# Kosmos-X3000-FM-Superregen.net
KiCad netlist of a schematic drawn in EAGLE
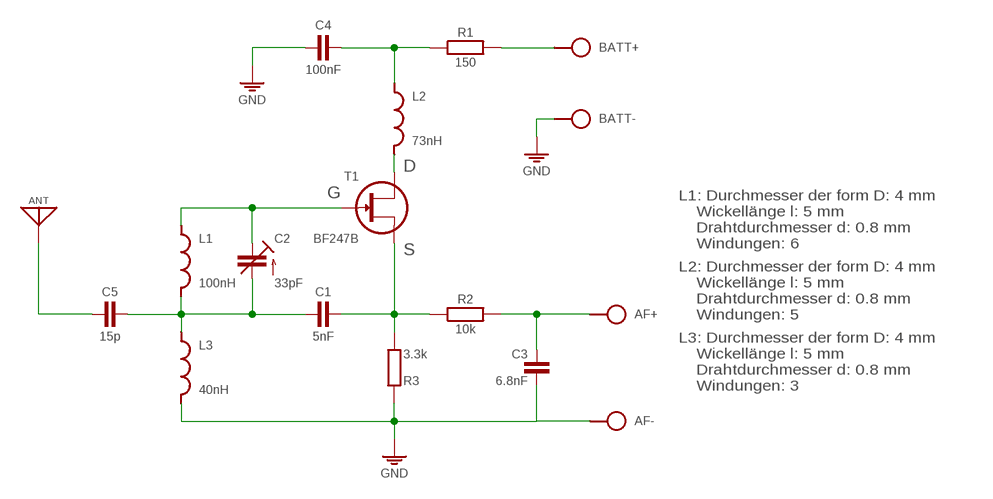
[diagram p0: schematic, sheet 1]

(export (version "E")
  (design (tool "Eeschema 10.0.6"))
  (components
    (comp (ref "AF")
      (value "SPAD+-+-")
      (footprint "eagle-import:SPAD+-")
      (libsource (lib "eagle-import") (part "SPAD+-+-"))
    )
    (comp (ref "ANT")
      (value "ANT")
      (footprint "eagle-import:SPAD")
      (libsource (lib "eagle-import") (part "ANT"))
    )
    (comp (ref "BATT")
      (value "SPAD+-+-")
      (footprint "eagle-import:SPAD+-")
      (libsource (lib "eagle-import") (part "SPAD+-+-"))
    )
    (comp (ref "C1")
      (value "5nF")
      (footprint "eagle-import:C050-020X044")
      (libsource (lib "eagle-import") (part "C050-020X044"))
    )
    (comp (ref "C2")
      (value "33pF")
      (footprint "eagle-import:TRIM-2222-808")
      (libsource (lib "eagle-import") (part "C-TR-PH201272222-808-2PIN"))
    )
    (comp (ref "C3")
      (value "6.8nF")
      (footprint "eagle-import:C050-020X044")
      (libsource (lib "eagle-import") (part "C050-020X044"))
    )
    (comp (ref "C4")
      (value "100nF")
      (footprint "eagle-import:C050-020X044")
      (libsource (lib "eagle-import") (part "C050-020X044"))
    )
    (comp (ref "C5")
      (value "15p")
      (footprint "eagle-import:C025-015X024")
      (libsource (lib "eagle-import") (part "C025-015X024"))
    )
    (comp (ref "L1")
      (value "100nH")
      (footprint "eagle-import:L-04-5_5V")
      (libsource (lib "eagle-import") (part "L-SHORT04-5/5V"))
    )
    (comp (ref "L2")
      (value "73nH")
      (footprint "eagle-import:L-04-5_5V")
      (libsource (lib "eagle-import") (part "L-SHORT04-5/5V"))
    )
    (comp (ref "L3")
      (value "40nH")
      (footprint "eagle-import:L-04-5_5V")
      (libsource (lib "eagle-import") (part "L-SHORT04-5/5V"))
    )
    (comp (ref "R1")
      (value "150")
      (footprint "eagle-import:0202_7-V")
      (libsource (lib "eagle-import") (part "R-H0202/7-V"))
    )
    (comp (ref "R2")
      (value "10k")
      (footprint "eagle-import:0202_7")
      (libsource (lib "eagle-import") (part "R-H0202/7"))
    )
    (comp (ref "R3")
      (value "3.3k")
      (footprint "eagle-import:0202_7")
      (libsource (lib "eagle-import") (part "R0202/7"))
    )
    (comp (ref "T1")
      (value "BF247B")
      (footprint "eagle-import:TO92")
      (libsource (lib "eagle-import") (part "BF247B"))
    )
  )
  (nets
    (net (code "1") (name "GND") (class "Default")
      (node (ref "AF") (pin "1") (pinfunction "P$1_1") (pintype "passive"))
      (node (ref "BATT") (pin "1") (pinfunction "P$1_1") (pintype "passive"))
      (node (ref "C3") (pin "2") (pinfunction "2_2") (pintype "passive"))
      (node (ref "C4") (pin "2") (pinfunction "2_2") (pintype "passive"))
      (node (ref "L3") (pin "1") (pinfunction "1_1") (pintype "passive"))
      (node (ref "R3") (pin "2") (pinfunction "1_2") (pintype "passive"))
    )
    (net (code "2") (name "Net-(AFA-P$1)") (class "Default")
      (node (ref "AF") (pin "2") (pinfunction "P$1_2") (pintype "passive"))
      (node (ref "C3") (pin "1") (pinfunction "1_1") (pintype "passive"))
      (node (ref "R2") (pin "2") (pinfunction "2_2") (pintype "passive"))
    )
    (net (code "3") (name "Net-(ANT-Pad1)") (class "Default")
      (node (ref "ANT") (pin "1") (pinfunction "1_1") (pintype "output"))
      (node (ref "C5") (pin "2") (pinfunction "2_2") (pintype "passive"))
    )
    (net (code "4") (name "Net-(BATTA-P$1)") (class "Default")
      (node (ref "BATT") (pin "2") (pinfunction "P$1_2") (pintype "passive"))
      (node (ref "R1") (pin "2") (pinfunction "2_2") (pintype "passive"))
    )
    (net (code "5") (name "Net-(C2-A)") (class "Default")
      (node (ref "C1") (pin "2") (pinfunction "2_2") (pintype "passive"))
      (node (ref "C2") (pin "2") (pinfunction "A_2") (pintype "passive"))
      (node (ref "C5") (pin "1") (pinfunction "1_1") (pintype "passive"))
      (node (ref "L1") (pin "1") (pinfunction "1_1") (pintype "passive"))
      (node (ref "L3") (pin "2") (pinfunction "2_2") (pintype "passive"))
    )
    (net (code "6") (name "Net-(C2-E)") (class "Default")
      (node (ref "C2") (pin "1") (pinfunction "E_1") (pintype "passive"))
      (node (ref "L1") (pin "2") (pinfunction "2_2") (pintype "passive"))
      (node (ref "T1") (pin "3") (pinfunction "G_3") (pintype "passive"))
    )
    (net (code "7") (name "Net-(C4-Pad1)") (class "Default")
      (node (ref "C4") (pin "1") (pinfunction "1_1") (pintype "passive"))
      (node (ref "L2") (pin "2") (pinfunction "2_2") (pintype "passive"))
      (node (ref "R1") (pin "1") (pinfunction "1_1") (pintype "passive"))
    )
    (net (code "8") (name "Net-(R3-2)") (class "Default")
      (node (ref "C1") (pin "1") (pinfunction "1_1") (pintype "passive"))
      (node (ref "R2") (pin "1") (pinfunction "1_1") (pintype "passive"))
      (node (ref "R3") (pin "1") (pinfunction "2_1") (pintype "passive"))
      (node (ref "T1") (pin "2") (pinfunction "S_2") (pintype "passive"))
    )
    (net (code "9") (name "Net-(T1-D)") (class "Default")
      (node (ref "L2") (pin "1") (pinfunction "1_1") (pintype "passive"))
      (node (ref "T1") (pin "1") (pinfunction "D_1") (pintype "passive"))
    )
  )
)
